# schematic-v2.net
KiCad netlist of a schematic drawn in EAGLE
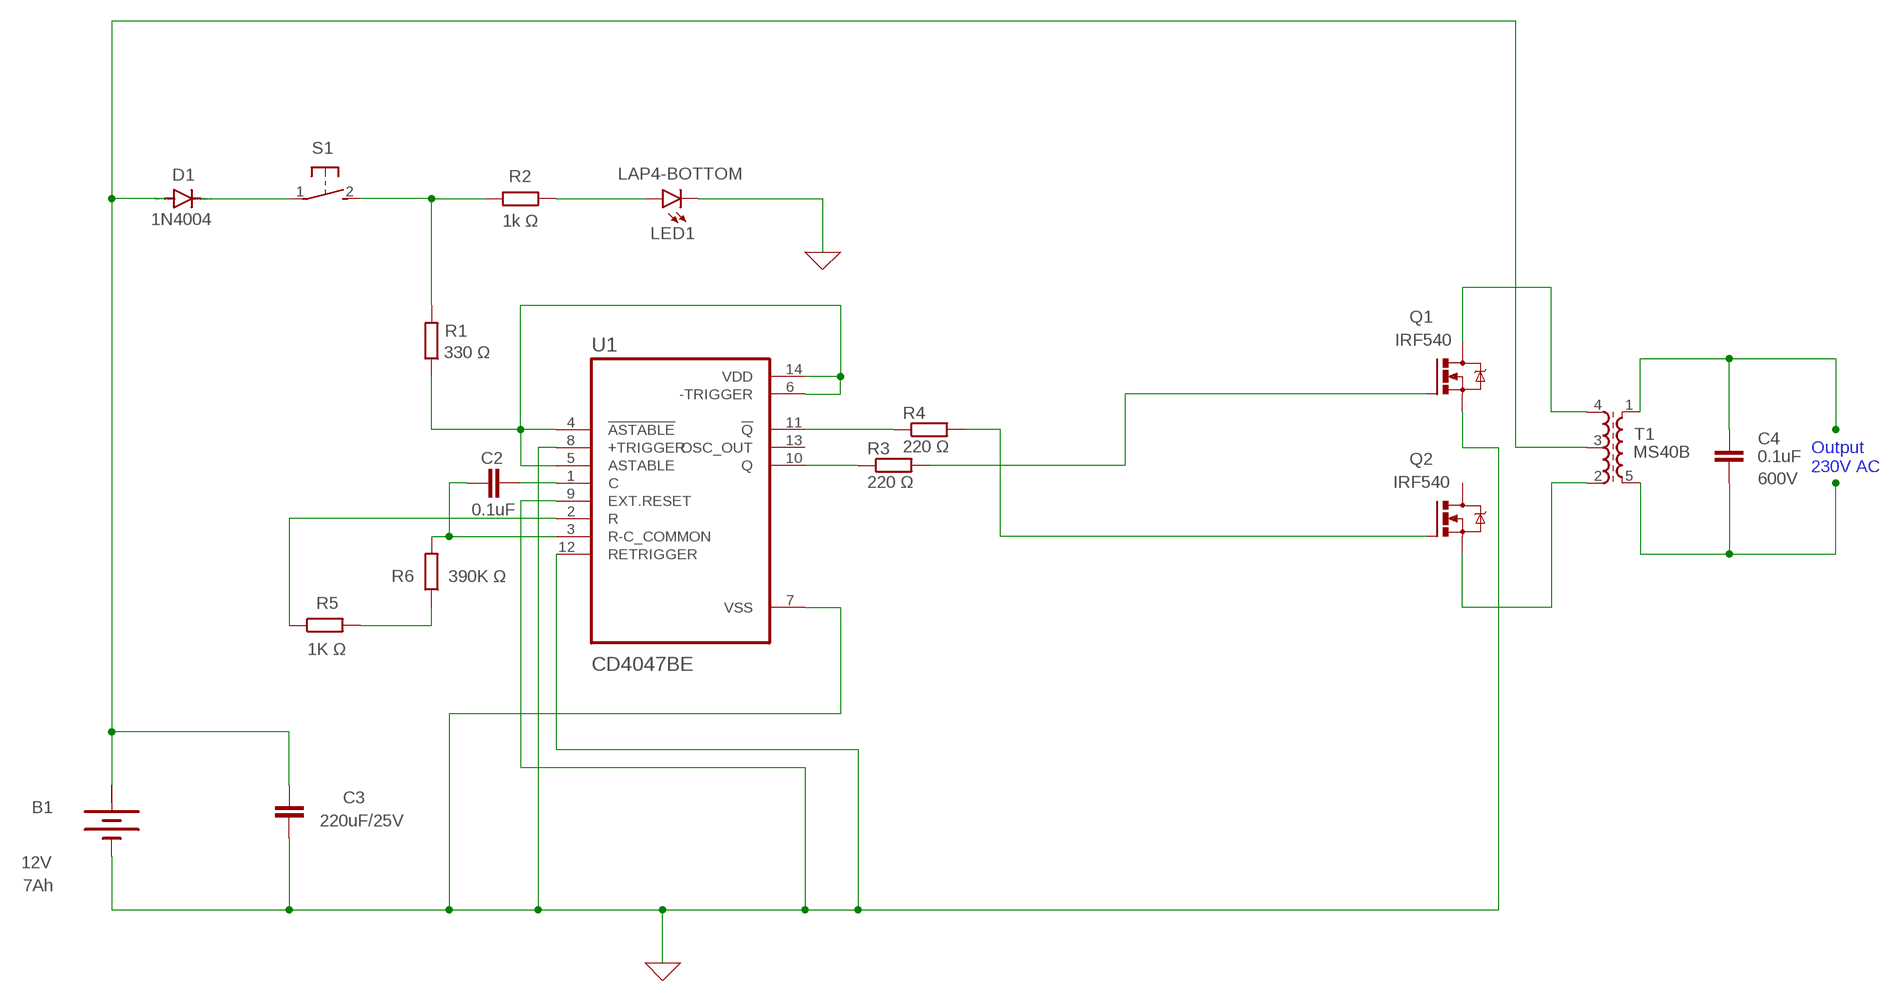
[diagram p0: schematic, sheet 1]

(export (version "E")
  (design (tool "Eeschema 10.0.6"))
  (components
    (comp (ref "B1")
      (value "12V")
      (footprint "eagle-import:BATTERY")
      (libsource (lib "eagle-import") (part "BATTERY"))
    )
    (comp (ref "C2")
      (value "0.1uF")
      (footprint "eagle-import:C2.5-3")
      (libsource (lib "eagle-import") (part "C2,5-3"))
    )
    (comp (ref "C3")
      (value "220uF/25V")
      (footprint "eagle-import:C2.5-3")
      (libsource (lib "eagle-import") (part "C2,5-3"))
    )
    (comp (ref "C4")
      (value "0.1uF")
      (footprint "eagle-import:C2.5-3")
      (libsource (lib "eagle-import") (part "C2,5-3"))
    )
    (comp (ref "D1")
      (value "1N4004")
      (footprint "eagle-import:DO41-10")
      (libsource (lib "eagle-import") (part "1N4004"))
    )
    (comp (ref "LED1")
      (value "LAP4-BOTTOM")
      (footprint "eagle-import:P47F-BOTTOM")
      (libsource (lib "eagle-import") (part "P4-BOTTOMLA"))
    )
    (comp (ref "Q1")
      (value "IRF540")
      (footprint "eagle-import:TO220BV")
      (libsource (lib "eagle-import") (part "IRF540"))
    )
    (comp (ref "Q2")
      (value "IRF540")
      (footprint "eagle-import:TO220BV")
      (libsource (lib "eagle-import") (part "IRF540"))
    )
    (comp (ref "R1")
      (value "330 Ω")
      (footprint "eagle-import:0204_7")
      (libsource (lib "eagle-import") (part "R-EU_0204/7"))
    )
    (comp (ref "R2")
      (value "1k Ω")
      (footprint "eagle-import:0204_7")
      (libsource (lib "eagle-import") (part "R-EU_0204/7"))
    )
    (comp (ref "R3")
      (value "220 Ω")
      (footprint "eagle-import:0204_7")
      (libsource (lib "eagle-import") (part "R-EU_0204/7"))
    )
    (comp (ref "R4")
      (value "220 Ω")
      (footprint "eagle-import:0204_7")
      (libsource (lib "eagle-import") (part "R-EU_0204/7"))
    )
    (comp (ref "R5")
      (value "1K Ω")
      (footprint "eagle-import:0204_7")
      (libsource (lib "eagle-import") (part "R-EU_0204/7"))
    )
    (comp (ref "R6")
      (value "390K Ω")
      (footprint "eagle-import:0204_7")
      (libsource (lib "eagle-import") (part "R-EU_0204/7"))
    )
    (comp (ref "S1")
      (value "31-XX")
      (footprint "eagle-import:B3F-31XX")
      (fields (field (name "MPN") "B3F-3100"))
      (libsource (lib "eagle-import") (part "31-XX"))
    )
    (comp (ref "T1")
      (value "MS40B")
      (footprint "eagle-import:MS40")
      (libsource (lib "eagle-import") (part "MS40B"))
    )
    (comp (ref "U1")
      (value "CD4047BE")
      (footprint "eagle-import:DIP794W45P254L1969H508Q14")
      (fields (field (name "MF") "Texas Instruments"))
      (libsource (lib "eagle-import") (part "CD4047BE"))
    )
  )
  (nets
    (net (code "1") (name "/+") (class "Default")
      (node (ref "B1") (pin "+@1") (pinfunction "+_+@1") (pintype "power_in"))
    )
    (net (code "2") (name "GND") (class "Default")
      (node (ref "B1") (pin "-") (pinfunction "-_-") (pintype "power_in"))
      (node (ref "C3") (pin "2") (pinfunction "2_2") (pintype "passive"))
      (node (ref "LED1") (pin "C") (pinfunction "C_C") (pintype "passive"))
      (node (ref "Q1") (pin "S") (pinfunction "S_S") (pintype "passive"))
      (node (ref "U1") (pin "12") (pinfunction "RETRIGGER_12") (pintype "input"))
      (node (ref "U1") (pin "7") (pinfunction "VSS_7") (pintype "power_in"))
      (node (ref "U1") (pin "8") (pinfunction "+TRIGGER_8") (pintype "input"))
      (node (ref "U1") (pin "9") (pinfunction "EXT.RESET_9") (pintype "input"))
    )
    (net (code "3") (name "Net-(B1-Pad+)") (class "Default")
      (node (ref "B1") (pin "+") (pinfunction "+_+") (pintype "power_in"))
      (node (ref "C3") (pin "1") (pinfunction "1_1") (pintype "passive"))
      (node (ref "D1") (pin "A") (pinfunction "A_A") (pintype "passive"))
      (node (ref "T1") (pin "3") (pinfunction "3_3") (pintype "passive"))
    )
    (net (code "4") (name "Net-(LED1-PadA)") (class "Default")
      (node (ref "LED1") (pin "A") (pinfunction "A_A") (pintype "passive"))
      (node (ref "R2") (pin "1") (pinfunction "1_1") (pintype "passive"))
    )
    (net (code "5") (name "Net-(Q1-PadD)") (class "Default")
      (node (ref "Q1") (pin "D") (pinfunction "D_D") (pintype "passive"))
      (node (ref "T1") (pin "4") (pinfunction "4_4") (pintype "passive"))
    )
    (net (code "6") (name "Net-(Q1-PadG)") (class "Default")
      (node (ref "Q1") (pin "G") (pinfunction "G_G") (pintype "passive"))
      (node (ref "R3") (pin "2") (pinfunction "2_2") (pintype "passive"))
    )
    (net (code "7") (name "Net-(Q2-PadG)") (class "Default")
      (node (ref "Q2") (pin "G") (pinfunction "G_G") (pintype "passive"))
      (node (ref "R4") (pin "2") (pinfunction "2_2") (pintype "passive"))
    )
    (net (code "8") (name "Net-(Q2-PadS)") (class "Default")
      (node (ref "Q2") (pin "S") (pinfunction "S_S") (pintype "passive"))
      (node (ref "T1") (pin "2") (pinfunction "2_2") (pintype "passive"))
    )
    (net (code "9") (name "Net-(R5-Pad2)") (class "Default")
      (node (ref "R5") (pin "2") (pinfunction "2_2") (pintype "passive"))
      (node (ref "R6") (pin "1") (pinfunction "1_1") (pintype "passive"))
    )
    (net (code "10") (name "Net-(S1-P)") (class "Default")
      (node (ref "D1") (pin "C") (pinfunction "C_C") (pintype "passive"))
      (node (ref "S1") (pin "1") (pinfunction "P_1") (pintype "passive"))
    )
    (net (code "11") (name "Net-(S1-S)") (class "Default")
      (node (ref "R1") (pin "2") (pinfunction "2_2") (pintype "passive"))
      (node (ref "R2") (pin "2") (pinfunction "2_2") (pintype "passive"))
      (node (ref "S1") (pin "2") (pinfunction "S_2") (pintype "passive"))
    )
    (net (code "12") (name "Net-(T1-1)") (class "Default")
      (node (ref "C4") (pin "2") (pinfunction "2_2") (pintype "passive"))
      (node (ref "T1") (pin "5") (pinfunction "1_5") (pintype "passive"))
    )
    (net (code "13") (name "Net-(T1-5)") (class "Default")
      (node (ref "C4") (pin "1") (pinfunction "1_1") (pintype "passive"))
      (node (ref "T1") (pin "1") (pinfunction "5_1") (pintype "passive"))
    )
    (net (code "14") (name "Net-(U1--TRIGGER)") (class "Default")
      (node (ref "R1") (pin "1") (pinfunction "1_1") (pintype "passive"))
      (node (ref "U1") (pin "14") (pinfunction "VDD_14") (pintype "power_in"))
      (node (ref "U1") (pin "4") (pinfunction "~{ASTABLE}_4") (pintype "input"))
      (node (ref "U1") (pin "5") (pinfunction "ASTABLE_5") (pintype "input"))
      (node (ref "U1") (pin "6") (pinfunction "-TRIGGER_6") (pintype "power_in"))
    )
    (net (code "15") (name "Net-(U1-C)") (class "Default")
      (node (ref "C2") (pin "2") (pinfunction "2_2") (pintype "passive"))
      (node (ref "U1") (pin "1") (pinfunction "C_1") (pintype "input"))
    )
    (net (code "16") (name "Net-(U1-Q)") (class "Default")
      (node (ref "R3") (pin "1") (pinfunction "1_1") (pintype "passive"))
      (node (ref "U1") (pin "10") (pinfunction "Q_10") (pintype "output"))
    )
    (net (code "17") (name "Net-(U1-R)") (class "Default")
      (node (ref "R5") (pin "1") (pinfunction "1_1") (pintype "passive"))
      (node (ref "U1") (pin "2") (pinfunction "R_2") (pintype "input"))
    )
    (net (code "18") (name "Net-(U1-R-C_COMMON)") (class "Default")
      (node (ref "C2") (pin "1") (pinfunction "1_1") (pintype "passive"))
      (node (ref "R6") (pin "2") (pinfunction "2_2") (pintype "passive"))
      (node (ref "U1") (pin "3") (pinfunction "R-C_COMMON_3") (pintype "input"))
    )
    (net (code "19") (name "Net-(U1-~{Q})") (class "Default")
      (node (ref "R4") (pin "1") (pinfunction "1_1") (pintype "passive"))
      (node (ref "U1") (pin "11") (pinfunction "~{Q}_11") (pintype "output"))
    )
    (net (code "20") (name "unconnected-(Q2-PadD)") (class "Default")
      (node (ref "Q2") (pin "D") (pinfunction "D_D") (pintype "passive"))
    )
    (net (code "21") (name "unconnected-(U1-OSC_OUT-Pad13)") (class "Default")
      (node (ref "U1") (pin "13") (pinfunction "OSC_OUT_13") (pintype "output"))
    )
  )
)
